# White_Noise.net
KiCad netlist of a schematic drawn in Altium Designer
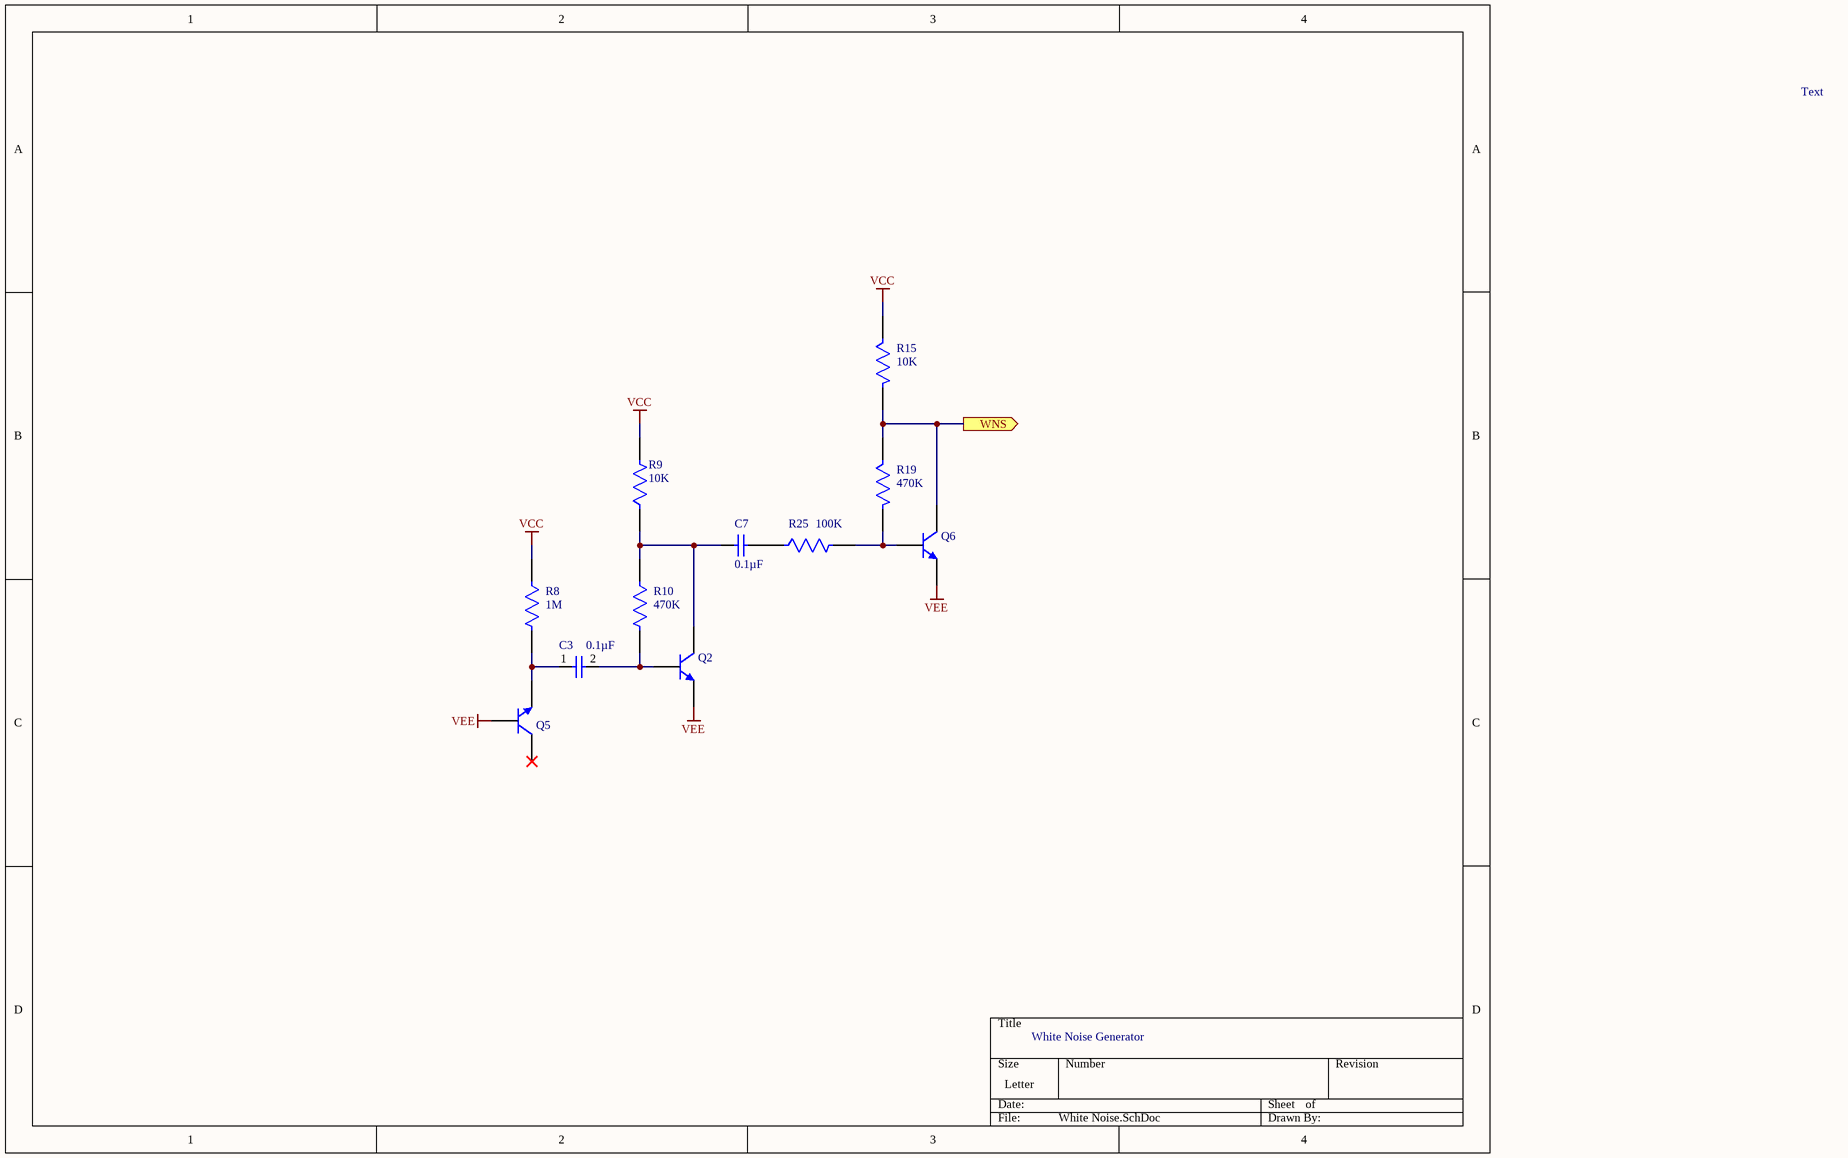
[diagram p0: White Noise.SchDoc]

(export (version "E")
  (design (tool "Eeschema 10.0.6"))
  (components
    (comp (ref "C3")
      (value "CL10B104KB8NNNC")
      (footprint "SAMS-C0603-2_M")
      (description "Multi-layer Ceramic Capacitor, -55 to 125 degC, 2-Pin SMD (0603), RoHS, Tape and Reel")
      (fields (field (name "CAPACITANCE") "0.1µF") (field (name "MANUFACTURER") "Samsung Electro-Mechanics"))
      (libsource (lib "") (part "CAP-NP-2_1"))
    )
    (comp (ref "C7")
      (value "CL10B104KB8NNNC")
      (footprint "SAMS-C0603-2_M")
      (description "Multi-layer Ceramic Capacitor, -55 to 125 degC, 2-Pin SMD (0603), RoHS, Tape and Reel")
      (fields (field (name "CAPACITANCE") "0.1µF") (field (name "MANUFACTURER") "Samsung Electro-Mechanics"))
      (libsource (lib "Altium Content Vault") (part "CAP-NP-2"))
    )
    (comp (ref "Q2")
      (value "MMBT3904LT1G")
      (footprint "ONSC-SOT-23-3-318-08_V")
      (description "General Purpose Transistor, NPN Silicon, 3-Pin SOT-23, Pb-Free, Tape and Reel")
      (fields
        (field (name "MANUFACTURER") "On Semiconductor")
        (field (name "MANUFACTURER PART NUMBER") "MMBT3904,215")
      )
      (libsource (lib "Altium Content Vault") (part "ONSC-NPN-B1E2C3-3"))
    )
    (comp (ref "Q5")
      (value "MMBT3904LT1G")
      (footprint "ONSC-SOT-23-3-318-08_V")
      (description "General Purpose Transistor, NPN Silicon, 3-Pin SOT-23, Pb-Free, Tape and Reel")
      (fields
        (field (name "MANUFACTURER") "On Semiconductor")
        (field (name "MANUFACTURER PART NUMBER") "MMBT3904,215")
      )
      (libsource (lib "Altium Content Vault") (part "ONSC-NPN-B1E2C3-3"))
    )
    (comp (ref "Q6")
      (value "MMBT3904LT1G")
      (footprint "ONSC-SOT-23-3-318-08_V")
      (description "General Purpose Transistor, NPN Silicon, 3-Pin SOT-23, Pb-Free, Tape and Reel")
      (fields
        (field (name "MANUFACTURER") "On Semiconductor")
        (field (name "MANUFACTURER PART NUMBER") "MMBT3904,215")
      )
      (libsource (lib "Altium Content Vault") (part "ONSC-NPN-B1E2C3-3"))
    )
    (comp (ref "R8")
      (value "ESR03EZPJ105")
      (footprint "FP-ESR03-IPC_B")
      (description "1MΩ ±5% 0.25W 0603 Anti-Surge Chip Resistor AEC-Q200")
      (fields (field (name "RESISTANCE") "1M") (field (name "TOLERANCE") "5%"))
      (libsource (lib "Altium Content Vault") (part "1029c3af85768c4190bb7ad29bc67b5"))
    )
    (comp (ref "R9")
      (value "ESR03EZPJ103")
      (footprint "FP-ESR03-IPC_B")
      (description "10kΩ ±5% 0.25W 0603 Anti-Surge Chip Resistor AEC-Q200")
      (fields (field (name "TOLERANCE") "5%") (field (name "RESISTANCE") "10K"))
      (libsource (lib "Altium Content Vault") (part "1029c3af85768c4190bb7ad29bc67b5"))
    )
    (comp (ref "R10")
      (value "ESR03EZPJ474")
      (footprint "FP-ESR03-IPC_B")
      (description "470kΩ ±5% 0.25W 0603 Anti-Surge Chip Resistor AEC-Q200")
      (fields (field (name "TOLERANCE") "5%") (field (name "RESISTANCE") "470K"))
      (libsource (lib "Altium Content Vault") (part "1029c3af85768c4190bb7ad29bc67b5"))
    )
    (comp (ref "R15")
      (value "ESR03EZPJ103")
      (footprint "FP-ESR03-IPC_B")
      (description "10kΩ ±5% 0.25W 0603 Anti-Surge Chip Resistor AEC-Q200")
      (fields (field (name "TOLERANCE") "5%") (field (name "RESISTANCE") "10K"))
      (libsource (lib "Altium Content Vault") (part "1029c3af85768c4190bb7ad29bc67b5"))
    )
    (comp (ref "R19")
      (value "ESR03EZPJ474")
      (footprint "FP-ESR03-IPC_B")
      (description "470kΩ ±5% 0.25W 0603 Anti-Surge Chip Resistor AEC-Q200")
      (fields (field (name "TOLERANCE") "5%") (field (name "RESISTANCE") "470K"))
      (libsource (lib "Altium Content Vault") (part "1029c3af85768c4190bb7ad29bc67b5"))
    )
    (comp (ref "R25")
      (value "ESR03EZPJ104")
      (footprint "FP-ESR03-IPC_B")
      (description "100kΩ ±5% 0.25W 0603 Anti-Surge Chip Resistor AEC-Q200")
      (fields (field (name "TOLERANCE") "5%") (field (name "RESISTANCE") "100K"))
      (libsource (lib "Altium Content Vault") (part "1029c3af85768c4190bb7ad29bc67b5"))
    )
  )
  (nets
    (net (code "1") (name "/WNS") (class "Default")
      (node (ref "Q6") (pin "3") (pinfunction "C_3") (pintype "passive"))
      (node (ref "R15") (pin "2") (pinfunction "2_2") (pintype "passive"))
      (node (ref "R19") (pin "1") (pinfunction "1_1") (pintype "passive"))
    )
    (net (code "2") (name "Net-(C7-Pad1)") (class "Default")
      (node (ref "C7") (pin "1") (pinfunction "1_1") (pintype "passive"))
      (node (ref "R25") (pin "1") (pinfunction "1_1") (pintype "passive"))
    )
    (net (code "3") (name "Net-(Q2-B)") (class "Default")
      (node (ref "C3") (pin "2") (pinfunction "2_2") (pintype "passive"))
      (node (ref "Q2") (pin "1") (pinfunction "B_1") (pintype "passive"))
      (node (ref "R10") (pin "2") (pinfunction "2_2") (pintype "passive"))
    )
    (net (code "4") (name "Net-(Q2-C)") (class "Default")
      (node (ref "C7") (pin "2") (pinfunction "2_2") (pintype "passive"))
      (node (ref "Q2") (pin "3") (pinfunction "C_3") (pintype "passive"))
      (node (ref "R10") (pin "1") (pinfunction "1_1") (pintype "passive"))
      (node (ref "R9") (pin "1") (pinfunction "1_1") (pintype "passive"))
    )
    (net (code "5") (name "Net-(Q5-E)") (class "Default")
      (node (ref "C3") (pin "1") (pinfunction "1_1") (pintype "passive"))
      (node (ref "Q5") (pin "2") (pinfunction "E_2") (pintype "passive"))
      (node (ref "R8") (pin "2") (pinfunction "2_2") (pintype "passive"))
    )
    (net (code "6") (name "Net-(Q6-B)") (class "Default")
      (node (ref "Q6") (pin "1") (pinfunction "B_1") (pintype "passive"))
      (node (ref "R19") (pin "2") (pinfunction "2_2") (pintype "passive"))
      (node (ref "R25") (pin "2") (pinfunction "2_2") (pintype "passive"))
    )
    (net (code "7") (name "VCC") (class "Default")
      (node (ref "R15") (pin "1") (pinfunction "1_1") (pintype "passive"))
      (node (ref "R8") (pin "1") (pinfunction "1_1") (pintype "passive"))
      (node (ref "R9") (pin "2") (pinfunction "2_2") (pintype "passive"))
    )
    (net (code "8") (name "VEE") (class "Default")
      (node (ref "Q2") (pin "2") (pinfunction "E_2") (pintype "passive"))
      (node (ref "Q5") (pin "1") (pinfunction "B_1") (pintype "passive"))
      (node (ref "Q6") (pin "2") (pinfunction "E_2") (pintype "passive"))
    )
    (net (code "9") (name "unconnected-(Q5-C-Pad3)") (class "Default")
      (node (ref "Q5") (pin "3") (pinfunction "C_3") (pintype "passive+no_connect"))
    )
  )
)
